# isolation.net
KiCad netlist of a schematic drawn in Altium Designer
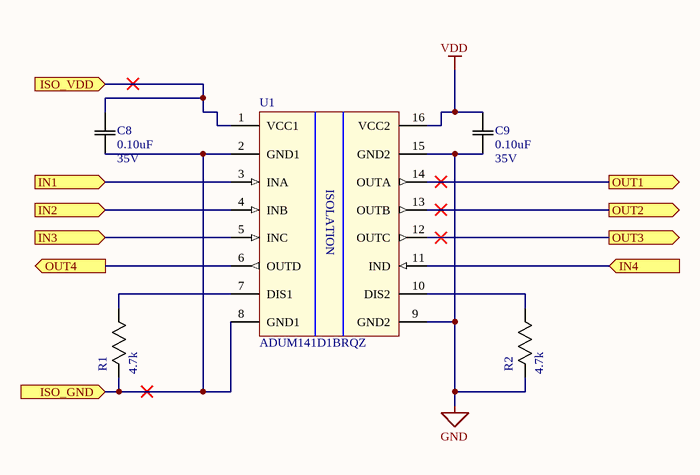
[diagram p0: isolation.SchDoc]

(export (version "E")
  (design (tool "Eeschema 10.0.6"))
  (components
    (comp (ref "C8")
      (value "0.10uF")
      (footprint "0603")
      (description "CAP CER 0.10UF 35V X7R 0603/0805")
      (fields (field (name "TOLERANCE") "10%") (field (name "RATING") "35V"))
      (libsource (lib "AltiumLibraries") (part "CAP 0.10uF 35V"))
    )
    (comp (ref "C9")
      (value "0.10uF")
      (footprint "0603")
      (description "CAP CER 0.10UF 35V X7R 0603/0805")
      (fields (field (name "TOLERANCE") "10%") (field (name "RATING") "35V"))
      (libsource (lib "AltiumLibraries") (part "CAP 0.10uF 35V"))
    )
    (comp (ref "R1")
      (value "4.7k")
      (footprint "0603")
      (description "RES SMD 4.7k OHM 5% 1/8W 0805")
      (fields (field (name "TOLERANCE") "5%"))
      (libsource (lib "AltiumLibraries") (part "RES 4.7k 1/8W - 5%"))
    )
    (comp (ref "R2")
      (value "4.7k")
      (footprint "0603")
      (description "RES SMD 4.7k OHM 5% 1/8W 0805")
      (fields (field (name "TOLERANCE") "5%"))
      (libsource (lib "AltiumLibraries") (part "RES 4.7k 1/8W - 5%"))
    )
    (comp (ref "U1")
      (value "ADUM141D1BRQZ")
      (footprint "SOP64P600X175-16N")
      (description "DGTL ISO 3.75KV 4CH SPI 16SSOP 3/1")
      (libsource (lib "AltiumLibraries") (part "ISO ADUM141D1BRQZ"))
    )
  )
  (nets
    (net (code "1") (name "/IN1") (class "Default")
      (node (ref "U1") (pin "3") (pinfunction "INA_3") (pintype "input"))
    )
    (net (code "2") (name "/IN2") (class "Default")
      (node (ref "U1") (pin "4") (pinfunction "INB_4") (pintype "input"))
    )
    (net (code "3") (name "/IN3") (class "Default")
      (node (ref "U1") (pin "5") (pinfunction "INC_5") (pintype "input"))
    )
    (net (code "4") (name "/IN4") (class "Default")
      (node (ref "U1") (pin "11") (pinfunction "IND_11") (pintype "input"))
    )
    (net (code "5") (name "/ISO_GND") (class "Default")
      (node (ref "C8") (pin "1") (pinfunction "C1_1") (pintype "passive"))
      (node (ref "R1") (pin "2") (pinfunction "R2_2") (pintype "passive"))
      (node (ref "U1") (pin "2") (pinfunction "GND1_2") (pintype "power_in"))
      (node (ref "U1") (pin "8") (pinfunction "GND1_8") (pintype "power_in"))
    )
    (net (code "6") (name "/ISO_VDD") (class "Default")
      (node (ref "C8") (pin "2") (pinfunction "C2_2") (pintype "passive"))
      (node (ref "U1") (pin "1") (pinfunction "VCC1_1") (pintype "power_in"))
    )
    (net (code "7") (name "/OUT1") (class "Default")
      (node (ref "U1") (pin "14") (pinfunction "OUTA_14") (pintype "output"))
    )
    (net (code "8") (name "/OUT2") (class "Default")
      (node (ref "U1") (pin "13") (pinfunction "OUTB_13") (pintype "output"))
    )
    (net (code "9") (name "/OUT3") (class "Default")
      (node (ref "U1") (pin "12") (pinfunction "OUTC_12") (pintype "output"))
    )
    (net (code "10") (name "/OUT4") (class "Default")
      (node (ref "U1") (pin "6") (pinfunction "OUTD_6") (pintype "output"))
    )
    (net (code "11") (name "GND") (class "Default")
      (node (ref "C9") (pin "1") (pinfunction "C1_1") (pintype "passive"))
      (node (ref "R2") (pin "2") (pinfunction "R2_2") (pintype "passive"))
      (node (ref "U1") (pin "15") (pinfunction "GND2_15") (pintype "power_in"))
      (node (ref "U1") (pin "9") (pinfunction "GND2_9") (pintype "power_in"))
    )
    (net (code "12") (name "Net-(R1-R1)") (class "Default")
      (node (ref "R1") (pin "1") (pinfunction "R1_1") (pintype "passive"))
      (node (ref "U1") (pin "7") (pinfunction "DIS1_7") (pintype "passive"))
    )
    (net (code "13") (name "Net-(R2-R1)") (class "Default")
      (node (ref "R2") (pin "1") (pinfunction "R1_1") (pintype "passive"))
      (node (ref "U1") (pin "10") (pinfunction "DIS2_10") (pintype "passive"))
    )
    (net (code "14") (name "VDD") (class "Default")
      (node (ref "C9") (pin "2") (pinfunction "C2_2") (pintype "passive"))
      (node (ref "U1") (pin "16") (pinfunction "VCC2_16") (pintype "power_in"))
    )
  )
)
